# Seven_Segment_Driver.net
KiCad netlist of a schematic drawn in Altium Designer
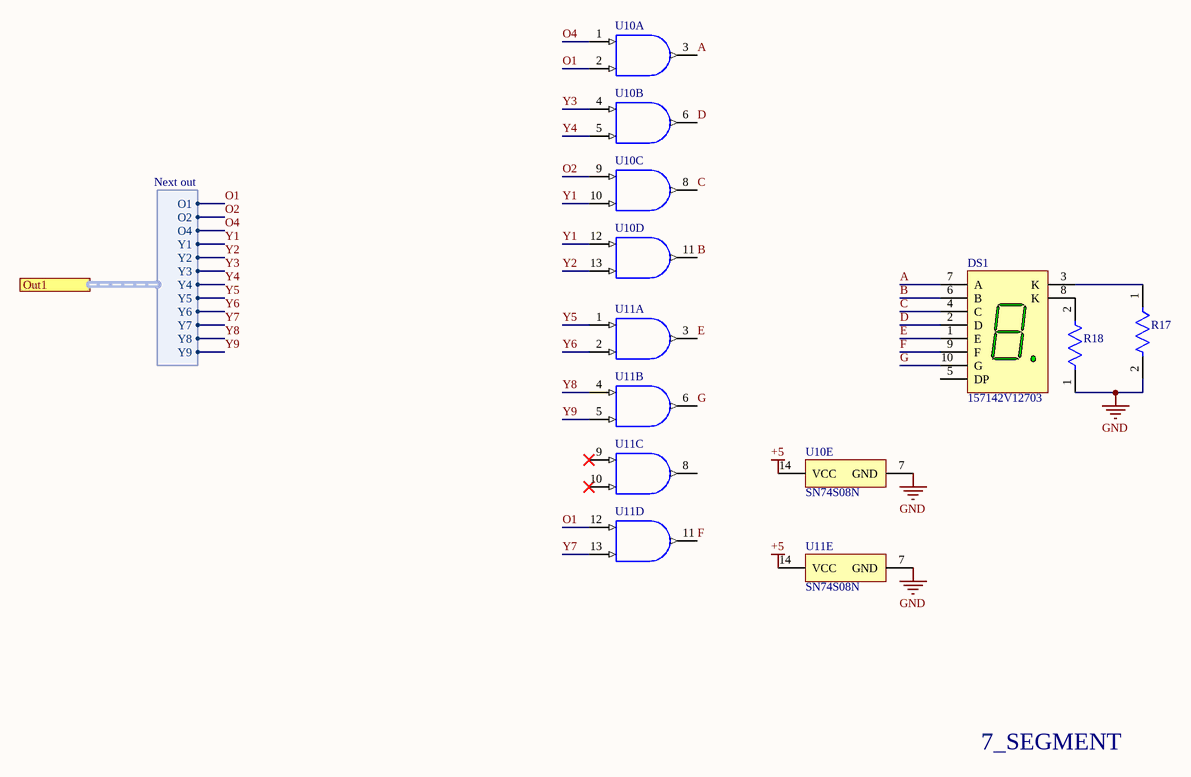
[diagram p0: Seven_Segment_Driver.SchDoc]

(export (version "E")
  (design (tool "Eeschema 10.0.6"))
  (components
    (comp (ref "DS1")
      (value "157142V12703")
      (footprint "WL-T7DS_L19W12.6H7.9")
      (description "157142V12703 7-Seg Display, Comm Cathode, Grn, 46Mcd Rohs Compliant: Yes")
      (libsource (lib "Altium Content Vault") (part "7 Segments_Green_CC_type 1"))
    )
    (comp (ref "R17")
      (value "MRS25000C1001FCT00")
      (footprint "FP-MRS25-MFG")
      (description "RES 1K OHM 0.6W 1% AXIAL")
      (fields (field (name "TOLERANCE") "1%"))
      (libsource (lib "Altium Content Vault") (part "1029c3af85768c4190bb7ad29bc67b5"))
    )
    (comp (ref "R18")
      (value "MRS25000C1001FCT00")
      (footprint "FP-MRS25-MFG")
      (description "RES 1K OHM 0.6W 1% AXIAL")
      (fields (field (name "TOLERANCE") "1%"))
      (libsource (lib "Altium Content Vault") (part "1029c3af85768c4190bb7ad29bc67b5"))
    )
    (comp (ref "U10")
      (value "SN74S08N")
      (footprint "N0014A")
      (description "Quad 2-input positive-AND gates, N0014A, TUBE")
      (fields
        (field (name "MANUFACTURER") "Texas Instruments")
        (field (name "GENERIC PART NUMBER") "SN74S08")
      )
      (libsource (lib "Altium Content Vault") (part "TI-AND-4-2IN-14"))
    )
    (comp (ref "U11")
      (value "SN74S08N")
      (footprint "N0014A")
      (description "Quad 2-input positive-AND gates, N0014A, TUBE")
      (fields
        (field (name "MANUFACTURER") "Texas Instruments")
        (field (name "GENERIC PART NUMBER") "SN74S08")
      )
      (libsource (lib "Altium Content Vault") (part "TI-AND-4-2IN-14"))
    )
  )
  (nets
    (net (code "3") (name "+5") (class "Default")
      (node (ref "U10") (pin "14") (pinfunction "VCC_14") (pintype "power_in"))
      (node (ref "U11") (pin "14") (pinfunction "VCC_14") (pintype "power_in"))
    )
    (net (code "4") (name "/A") (class "Default")
      (node (ref "DS1") (pin "7") (pinfunction "A_7") (pintype "passive"))
      (node (ref "U10") (pin "3") (pinfunction "1Y_3") (pintype "output"))
    )
    (net (code "5") (name "/B") (class "Default")
      (node (ref "DS1") (pin "6") (pinfunction "B_6") (pintype "passive"))
      (node (ref "U10") (pin "11") (pinfunction "4Y_11") (pintype "output"))
    )
    (net (code "6") (name "/C") (class "Default")
      (node (ref "DS1") (pin "4") (pinfunction "C_4") (pintype "passive"))
      (node (ref "U10") (pin "8") (pinfunction "3Y_8") (pintype "output"))
    )
    (net (code "7") (name "/D") (class "Default")
      (node (ref "DS1") (pin "2") (pinfunction "D_2") (pintype "passive"))
      (node (ref "U10") (pin "6") (pinfunction "2Y_6") (pintype "output"))
    )
    (net (code "8") (name "/E") (class "Default")
      (node (ref "DS1") (pin "1") (pinfunction "E_1") (pintype "passive"))
      (node (ref "U11") (pin "3") (pinfunction "1Y_3") (pintype "output"))
    )
    (net (code "9") (name "/F") (class "Default")
      (node (ref "DS1") (pin "9") (pinfunction "F_9") (pintype "passive"))
      (node (ref "U11") (pin "11") (pinfunction "4Y_11") (pintype "output"))
    )
    (net (code "10") (name "/G") (class "Default")
      (node (ref "DS1") (pin "10") (pinfunction "G_10") (pintype "passive"))
      (node (ref "U11") (pin "6") (pinfunction "2Y_6") (pintype "output"))
    )
    (net (code "11") (name "/O1") (class "Default")
      (node (ref "U10") (pin "2") (pinfunction "1B_2") (pintype "input"))
      (node (ref "U11") (pin "12") (pinfunction "4A_12") (pintype "input"))
    )
    (net (code "12") (name "/O2") (class "Default")
      (node (ref "U10") (pin "9") (pinfunction "3A_9") (pintype "input"))
    )
    (net (code "13") (name "/O4") (class "Default")
      (node (ref "U10") (pin "1") (pinfunction "1A_1") (pintype "input"))
    )
    (net (code "14") (name "/Y1") (class "Default")
      (node (ref "U10") (pin "10") (pinfunction "3B_10") (pintype "input"))
      (node (ref "U10") (pin "12") (pinfunction "4A_12") (pintype "input"))
    )
    (net (code "15") (name "/Y2") (class "Default")
      (node (ref "U10") (pin "13") (pinfunction "4B_13") (pintype "input"))
    )
    (net (code "16") (name "/Y3") (class "Default")
      (node (ref "U10") (pin "4") (pinfunction "2A_4") (pintype "input"))
    )
    (net (code "17") (name "/Y4") (class "Default")
      (node (ref "U10") (pin "5") (pinfunction "2B_5") (pintype "input"))
    )
    (net (code "18") (name "/Y5") (class "Default")
      (node (ref "U11") (pin "1") (pinfunction "1A_1") (pintype "input"))
    )
    (net (code "19") (name "/Y6") (class "Default")
      (node (ref "U11") (pin "2") (pinfunction "1B_2") (pintype "input"))
    )
    (net (code "20") (name "/Y7") (class "Default")
      (node (ref "U11") (pin "13") (pinfunction "4B_13") (pintype "input"))
    )
    (net (code "21") (name "/Y8") (class "Default")
      (node (ref "U11") (pin "4") (pinfunction "2A_4") (pintype "input"))
    )
    (net (code "22") (name "/Y9") (class "Default")
      (node (ref "U11") (pin "5") (pinfunction "2B_5") (pintype "input"))
    )
    (net (code "24") (name "GND") (class "Default")
      (node (ref "R17") (pin "2") (pinfunction "2_2") (pintype "passive"))
      (node (ref "R18") (pin "1") (pinfunction "1_1") (pintype "passive"))
      (node (ref "U10") (pin "7") (pinfunction "GND_7") (pintype "power_in"))
      (node (ref "U11") (pin "7") (pinfunction "GND_7") (pintype "power_in"))
    )
    (net (code "25") (name "Net-(DS1-K-Pad3)") (class "Default")
      (node (ref "DS1") (pin "3") (pinfunction "K_3") (pintype "passive"))
      (node (ref "R17") (pin "1") (pinfunction "1_1") (pintype "passive"))
    )
    (net (code "26") (name "Net-(DS1-K-Pad8)") (class "Default")
      (node (ref "DS1") (pin "8") (pinfunction "K_8") (pintype "passive"))
      (node (ref "R18") (pin "2") (pinfunction "2_2") (pintype "passive"))
    )
    (net (code "27") (name "unconnected-(DS1-DP-Pad5)") (class "Default")
      (node (ref "DS1") (pin "5") (pinfunction "DP_5") (pintype "passive"))
    )
    (net (code "28") (name "unconnected-(U11C-3A-Pad9)") (class "Default")
      (node (ref "U11") (pin "9") (pinfunction "3A_9") (pintype "input+no_connect"))
    )
    (net (code "29") (name "unconnected-(U11C-3B-Pad10)") (class "Default")
      (node (ref "U11") (pin "10") (pinfunction "3B_10") (pintype "input+no_connect"))
    )
    (net (code "30") (name "unconnected-(U11C-3Y-Pad8)") (class "Default")
      (node (ref "U11") (pin "8") (pinfunction "3Y_8") (pintype "output"))
    )
  )
)
